# 02_ESP12_CORE.net
KiCad netlist of a schematic drawn in Altium Designer
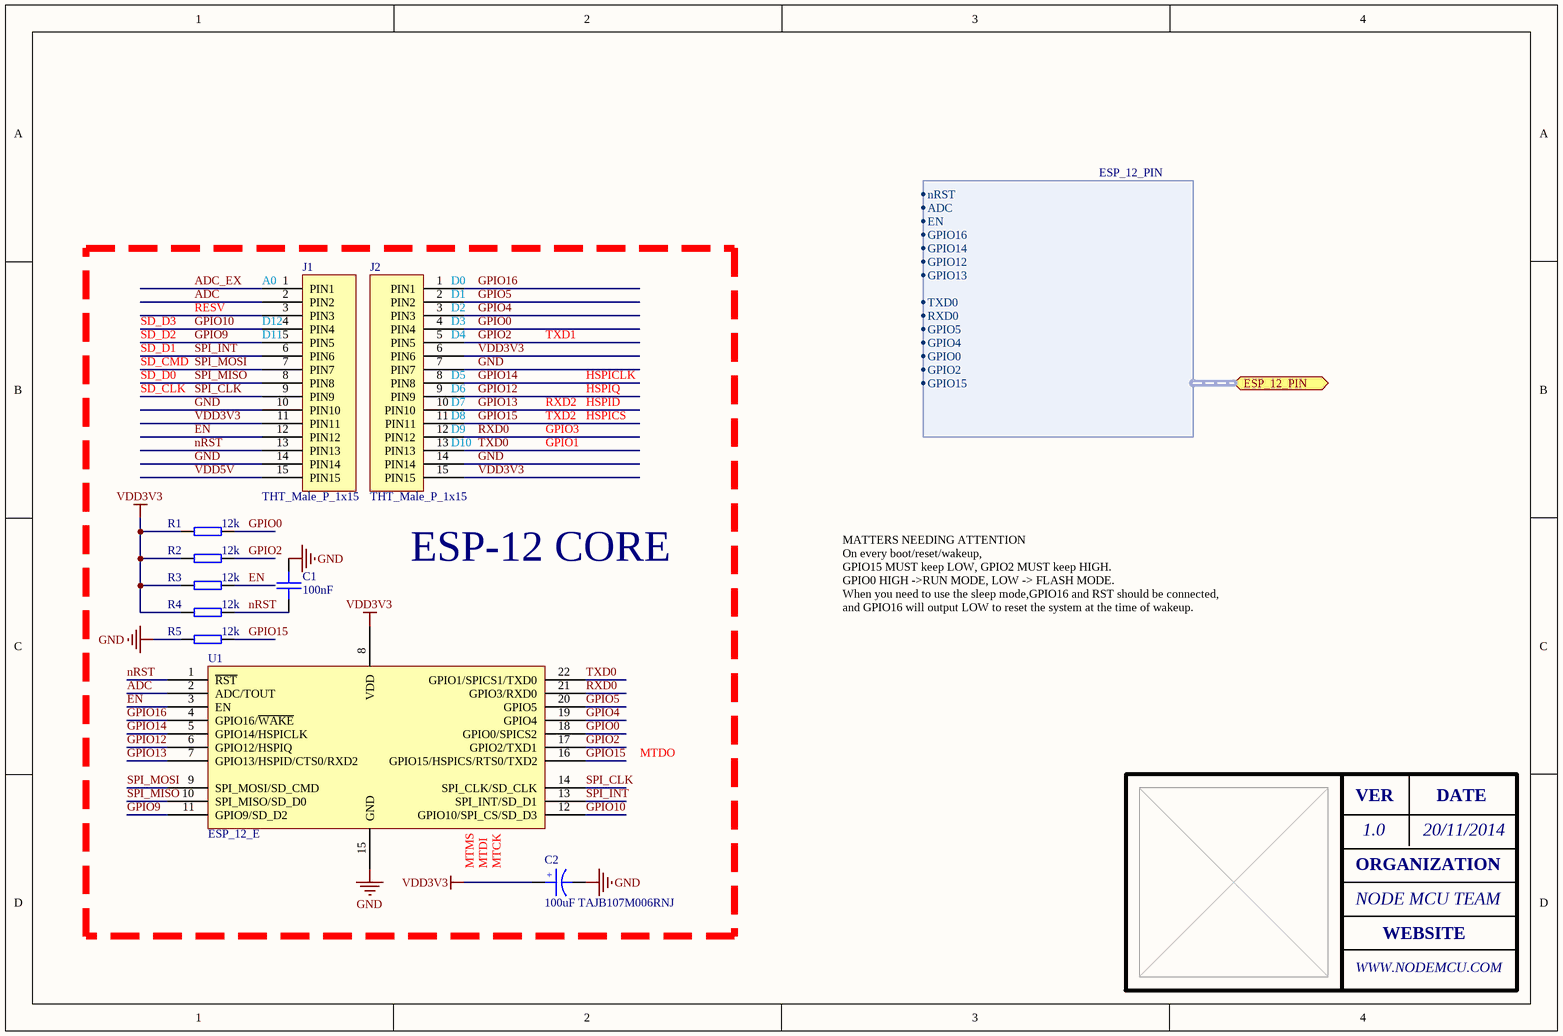
[diagram p0: 02_ESP12_CORE.SchDoc]

(export (version "E")
  (design (tool "Eeschema 10.0.6"))
  (components
    (comp (ref "C1")
      (value "100nF")
      (footprint "SMT_C_0402")
      (description "Surface mount capacitor 0402")
      (libsource (lib "Vowstar_Basic_Device") (part "SMT_C_0402"))
    )
    (comp (ref "C2")
      (value "100uF TAJB107M006RNJ")
      (footprint "SMT_C_Tantalum_B")
      (description "Capacitor, SM Tantalum; Body 3.5 x 2.8 mm (LxW typ)")
      (libsource (lib "Vowstar_Basic_Device") (part "SMT_C_Tantalum_B"))
    )
    (comp (ref "J1")
      (value "THT_Male_P_1x15")
      (footprint "THT_Male_P_1x15-2.54mm")
      (description "THT Male pin header strip 1x15")
      (libsource (lib "Vowstar_Connector") (part "THT_Male_P_1x15"))
    )
    (comp (ref "J2")
      (value "THT_Male_P_1x15")
      (footprint "THT_Male_P_1x15-2.54mm")
      (description "THT Male pin header strip 1x15")
      (libsource (lib "") (part "THT_Male_P_1x15_1"))
    )
    (comp (ref "R1")
      (value "12k")
      (footprint "SMT_R_0402")
      (description "Surface mount resistor 0402")
      (libsource (lib "Vowstar_Basic_Device") (part "SMT_R_0402"))
    )
    (comp (ref "R2")
      (value "12k")
      (footprint "SMT_R_0402")
      (description "Surface mount resistor 0402")
      (libsource (lib "Vowstar_Basic_Device") (part "SMT_R_0402"))
    )
    (comp (ref "R3")
      (value "12k")
      (footprint "SMT_R_0402")
      (description "Surface mount resistor 0402")
      (libsource (lib "Vowstar_Basic_Device") (part "SMT_R_0402"))
    )
    (comp (ref "R4")
      (value "12k")
      (footprint "SMT_R_0402")
      (description "Surface mount resistor 0402")
      (libsource (lib "Vowstar_Basic_Device") (part "SMT_R_0402"))
    )
    (comp (ref "R5")
      (value "12k")
      (footprint "SMT_R_0402")
      (description "Surface mount resistor 0402")
      (libsource (lib "Vowstar_Basic_Device") (part "SMT_R_0402"))
    )
    (comp (ref "U1")
      (value "ESP_12_E")
      (footprint "ESP_12_E_L")
      (description "ESP-12 Wi-Fi Module by AI-Thinker")
      (libsource (lib "Vowstar_Module") (part "ESP_12_E"))
    )
  )
  (nets
    (net (code "2") (name "/ADC") (class "Default")
      (node (ref "J1") (pin "2") (pinfunction "PIN2_2") (pintype "passive"))
      (node (ref "U1") (pin "2") (pinfunction "ADC/TOUT_2") (pintype "passive"))
    )
    (net (code "3") (name "/ADC_EX") (class "Default")
      (node (ref "J1") (pin "1") (pinfunction "PIN1_1") (pintype "passive"))
    )
    (net (code "4") (name "/EN") (class "Default")
      (node (ref "J1") (pin "12") (pinfunction "PIN12_12") (pintype "passive"))
      (node (ref "R3") (pin "2") (pinfunction "2_2") (pintype "passive"))
      (node (ref "U1") (pin "3") (pinfunction "EN_3") (pintype "passive"))
    )
    (net (code "5") (name "/GPIO0") (class "Default")
      (node (ref "J2") (pin "4") (pinfunction "PIN4_4") (pintype "passive"))
      (node (ref "R1") (pin "2") (pinfunction "2_2") (pintype "passive"))
      (node (ref "U1") (pin "18") (pinfunction "GPIO0/SPICS2_18") (pintype "passive"))
    )
    (net (code "6") (name "/GPIO2") (class "Default")
      (node (ref "J2") (pin "5") (pinfunction "PIN5_5") (pintype "passive"))
      (node (ref "R2") (pin "2") (pinfunction "2_2") (pintype "passive"))
      (node (ref "U1") (pin "17") (pinfunction "GPIO2/TXD1_17") (pintype "passive"))
    )
    (net (code "7") (name "/GPIO4") (class "Default")
      (node (ref "J2") (pin "3") (pinfunction "PIN3_3") (pintype "passive"))
      (node (ref "U1") (pin "19") (pinfunction "GPIO4_19") (pintype "passive"))
    )
    (net (code "8") (name "/GPIO5") (class "Default")
      (node (ref "J2") (pin "2") (pinfunction "PIN2_2") (pintype "passive"))
      (node (ref "U1") (pin "20") (pinfunction "GPIO5_20") (pintype "passive"))
    )
    (net (code "9") (name "/GPIO9") (class "Default")
      (node (ref "J1") (pin "5") (pinfunction "PIN5_5") (pintype "passive"))
      (node (ref "U1") (pin "11") (pinfunction "GPIO9/SD_D2_11") (pintype "passive"))
    )
    (net (code "10") (name "/GPIO10") (class "Default")
      (node (ref "J1") (pin "4") (pinfunction "PIN4_4") (pintype "passive"))
      (node (ref "U1") (pin "12") (pinfunction "GPIO10/SPI_CS/SD_D3_12") (pintype "passive"))
    )
    (net (code "11") (name "/GPIO12") (class "Default")
      (node (ref "J2") (pin "9") (pinfunction "PIN9_9") (pintype "passive"))
      (node (ref "U1") (pin "6") (pinfunction "GPIO12/HSPIQ_6") (pintype "passive"))
    )
    (net (code "12") (name "/GPIO13") (class "Default")
      (node (ref "J2") (pin "10") (pinfunction "PIN10_10") (pintype "passive"))
      (node (ref "U1") (pin "7") (pinfunction "GPIO13/HSPID/CTS0/RXD2_7") (pintype "passive"))
    )
    (net (code "13") (name "/GPIO14") (class "Default")
      (node (ref "J2") (pin "8") (pinfunction "PIN8_8") (pintype "passive"))
      (node (ref "U1") (pin "5") (pinfunction "GPIO14/HSPICLK_5") (pintype "passive"))
    )
    (net (code "14") (name "/GPIO15") (class "Default")
      (node (ref "J2") (pin "11") (pinfunction "PIN11_11") (pintype "passive"))
      (node (ref "R5") (pin "2") (pinfunction "2_2") (pintype "passive"))
      (node (ref "U1") (pin "16") (pinfunction "GPIO15/HSPICS/RTS0/TXD2_16") (pintype "passive"))
    )
    (net (code "15") (name "/GPIO16") (class "Default")
      (node (ref "J2") (pin "1") (pinfunction "PIN1_1") (pintype "passive"))
      (node (ref "U1") (pin "4") (pinfunction "GPIO16/~{WAKE}_4") (pintype "passive"))
    )
    (net (code "16") (name "/RXD0") (class "Default")
      (node (ref "J2") (pin "12") (pinfunction "PIN12_12") (pintype "passive"))
      (node (ref "U1") (pin "21") (pinfunction "GPIO3/RXD0_21") (pintype "passive"))
    )
    (net (code "17") (name "/SPI_CLK") (class "Default")
      (node (ref "J1") (pin "9") (pinfunction "PIN9_9") (pintype "passive"))
      (node (ref "U1") (pin "14") (pinfunction "SPI_CLK/SD_CLK_14") (pintype "passive"))
    )
    (net (code "18") (name "/SPI_INT") (class "Default")
      (node (ref "J1") (pin "6") (pinfunction "PIN6_6") (pintype "passive"))
      (node (ref "U1") (pin "13") (pinfunction "SPI_INT/SD_D1_13") (pintype "passive"))
    )
    (net (code "19") (name "/SPI_MISO") (class "Default")
      (node (ref "J1") (pin "8") (pinfunction "PIN8_8") (pintype "passive"))
      (node (ref "U1") (pin "10") (pinfunction "SPI_MISO/SD_D0_10") (pintype "passive"))
    )
    (net (code "20") (name "/SPI_MOSI") (class "Default")
      (node (ref "J1") (pin "7") (pinfunction "PIN7_7") (pintype "passive"))
      (node (ref "U1") (pin "9") (pinfunction "SPI_MOSI/SD_CMD_9") (pintype "passive"))
    )
    (net (code "21") (name "/TXD0") (class "Default")
      (node (ref "J2") (pin "13") (pinfunction "PIN13_13") (pintype "passive"))
      (node (ref "U1") (pin "22") (pinfunction "GPIO1/SPICS1/TXD0_22") (pintype "passive"))
    )
    (net (code "22") (name "/VDD5V") (class "Default")
      (node (ref "J1") (pin "15") (pinfunction "PIN15_15") (pintype "passive"))
    )
    (net (code "23") (name "/nRST") (class "Default")
      (node (ref "C1") (pin "1") (pinfunction "1_1") (pintype "passive"))
      (node (ref "J1") (pin "13") (pinfunction "PIN13_13") (pintype "passive"))
      (node (ref "R4") (pin "2") (pinfunction "2_2") (pintype "passive"))
      (node (ref "U1") (pin "1") (pinfunction "~{RST}_1") (pintype "passive"))
    )
    (net (code "25") (name "GND") (class "Default")
      (node (ref "C1") (pin "2") (pinfunction "2_2") (pintype "passive"))
      (node (ref "C2") (pin "2") (pinfunction "2_2") (pintype "passive"))
      (node (ref "J1") (pin "10") (pinfunction "PIN10_10") (pintype "passive"))
      (node (ref "J1") (pin "14") (pinfunction "PIN14_14") (pintype "passive"))
      (node (ref "J2") (pin "14") (pinfunction "PIN14_14") (pintype "passive"))
      (node (ref "J2") (pin "7") (pinfunction "PIN7_7") (pintype "passive"))
      (node (ref "R5") (pin "1") (pinfunction "1_1") (pintype "passive"))
      (node (ref "U1") (pin "15") (pinfunction "GND_15") (pintype "passive"))
    )
    (net (code "26") (name "VDD3V3") (class "Default")
      (node (ref "C2") (pin "1") (pinfunction "1_1") (pintype "passive"))
      (node (ref "J1") (pin "11") (pinfunction "PIN11_11") (pintype "passive"))
      (node (ref "J2") (pin "15") (pinfunction "PIN15_15") (pintype "passive"))
      (node (ref "J2") (pin "6") (pinfunction "PIN6_6") (pintype "passive"))
      (node (ref "R1") (pin "1") (pinfunction "1_1") (pintype "passive"))
      (node (ref "R2") (pin "1") (pinfunction "1_1") (pintype "passive"))
      (node (ref "R3") (pin "1") (pinfunction "1_1") (pintype "passive"))
      (node (ref "R4") (pin "1") (pinfunction "1_1") (pintype "passive"))
      (node (ref "U1") (pin "8") (pinfunction "VDD_8") (pintype "passive"))
    )
    (net (code "27") (name "unconnected-(J1-PIN3-Pad3)") (class "Default")
      (node (ref "J1") (pin "3") (pinfunction "PIN3_3") (pintype "passive"))
    )
  )
)
